# car.net
KiCad netlist of a schematic drawn in Altium Designer
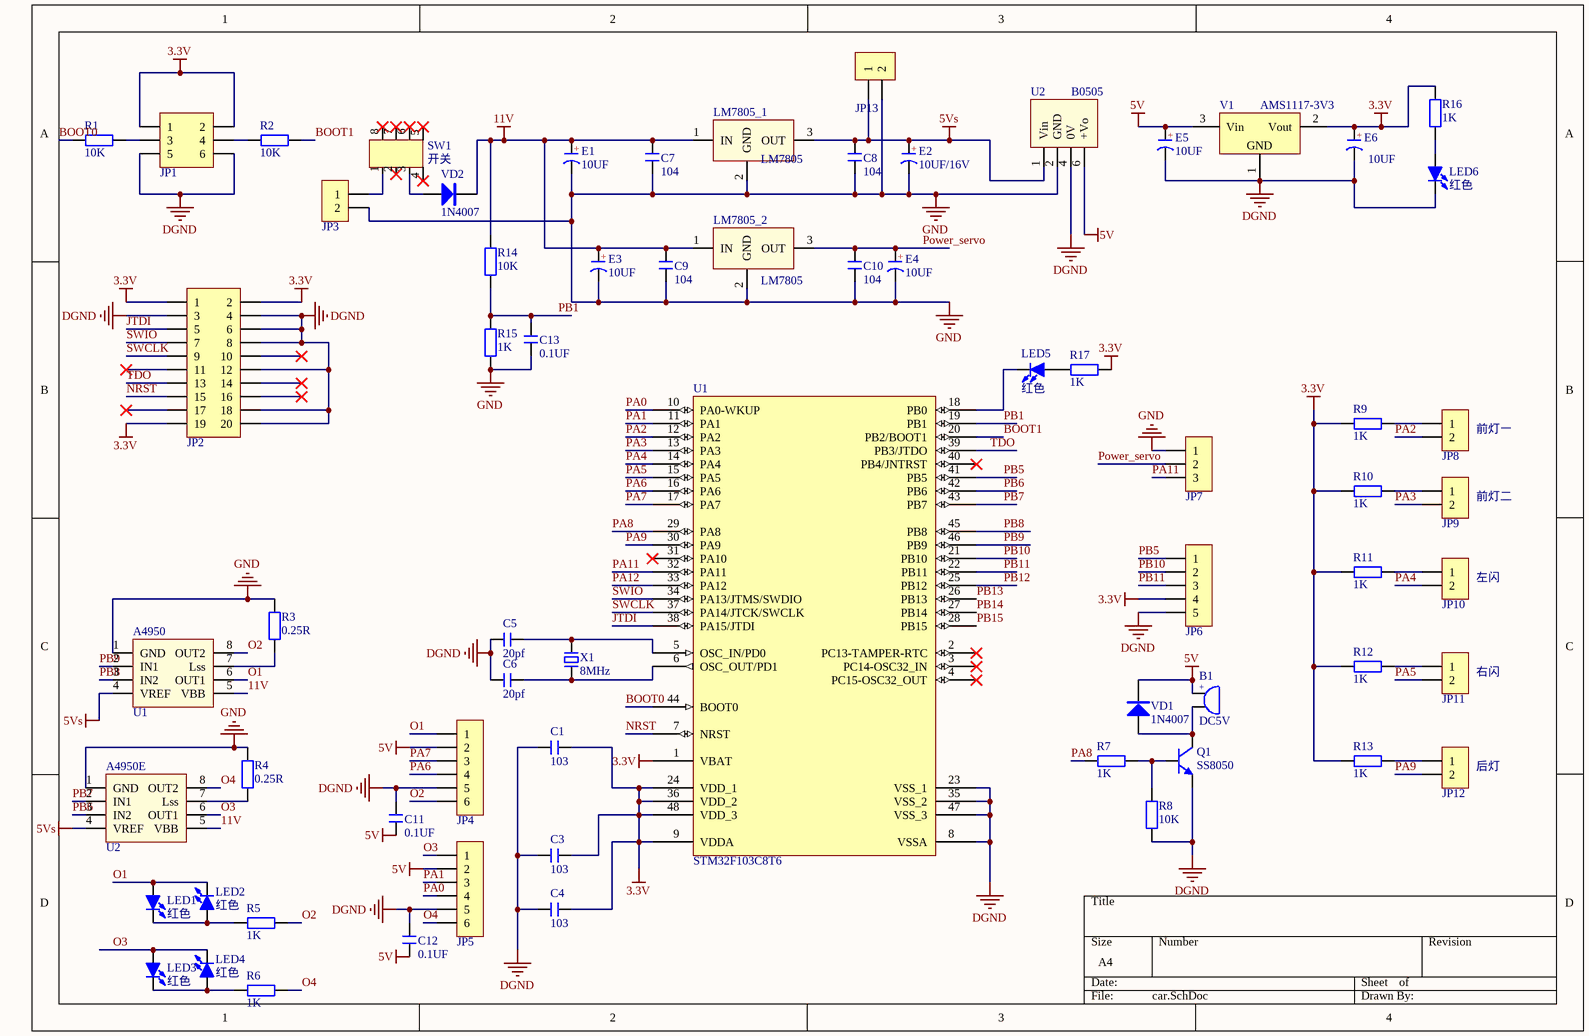
[diagram p0: car.SchDoc]

(export (version "E")
  (design (tool "Eeschema 10.0.6"))
  (components
    (comp (ref "A4950")
      (value "U1")
      (footprint "LC-SOIC-8_EP_150mil")
      (libsource (lib "A4950") (part "A4950"))
    )
    (comp (ref "A4950E")
      (value "U2")
      (footprint "LC-SOIC-8_EP_150mil")
      (libsource (lib "A4950") (part "A4950"))
    )
    (comp (ref "B1")
      (value "DC5V")
      (footprint "BEEP 7.6X12X9.5")
      (description "蜂鸣器")
      (fields (field (name "版权归属") "源创客"))
      (libsource (lib "未分类器件") (part "BEEP"))
    )
    (comp (ref "C1")
      (value "103")
      (footprint "C 0805")
      (description "无极性贴片电容")
      (fields (field (name "版权归属") "源创客"))
      (libsource (lib "电阻-电容-电感") (part "C"))
    )
    (comp (ref "C3")
      (value "103")
      (footprint "C 0805")
      (description "无极性贴片电容")
      (fields (field (name "版权归属") "源创客"))
      (libsource (lib "电阻-电容-电感") (part "C"))
    )
    (comp (ref "C4")
      (value "103")
      (footprint "C 0805")
      (description "无极性贴片电容")
      (fields (field (name "版权归属") "源创客"))
      (libsource (lib "电阻-电容-电感") (part "C"))
    )
    (comp (ref "C5")
      (value "20pf")
      (footprint "C 0805")
      (description "无极性贴片电容")
      (fields (field (name "版权归属") "源创客"))
      (libsource (lib "电阻-电容-电感") (part "C"))
    )
    (comp (ref "C6")
      (value "20pf")
      (footprint "C 0805")
      (description "无极性贴片电容")
      (fields (field (name "版权归属") "源创客"))
      (libsource (lib "电阻-电容-电感") (part "C"))
    )
    (comp (ref "C7")
      (value "104")
      (footprint "C 0805")
      (description "无极性贴片电容")
      (fields (field (name "版权归属") "源创客"))
      (libsource (lib "电阻-电容-电感") (part "C"))
    )
    (comp (ref "C8")
      (value "104")
      (footprint "C 0805")
      (description "无极性贴片电容")
      (fields (field (name "版权归属") "源创客"))
      (libsource (lib "电阻-电容-电感") (part "C"))
    )
    (comp (ref "C9")
      (value "104")
      (footprint "C 0805")
      (description "无极性贴片电容")
      (fields (field (name "版权归属") "源创客"))
      (libsource (lib "电阻-电容-电感") (part "C"))
    )
    (comp (ref "C10")
      (value "104")
      (footprint "C 0805")
      (description "无极性贴片电容")
      (fields (field (name "版权归属") "源创客"))
      (libsource (lib "电阻-电容-电感") (part "C"))
    )
    (comp (ref "C11")
      (value "0.1UF")
      (footprint "C 0805")
      (description "无极性贴片电容")
      (fields (field (name "版权归属") "源创客"))
      (libsource (lib "电阻-电容-电感") (part "C"))
    )
    (comp (ref "C12")
      (value "0.1UF")
      (footprint "C 0805")
      (description "无极性贴片电容")
      (fields (field (name "版权归属") "源创客"))
      (libsource (lib "电阻-电容-电感") (part "C"))
    )
    (comp (ref "C13")
      (value "0.1UF")
      (footprint "C 0805")
      (description "无极性贴片电容")
      (fields (field (name "版权归属") "源创客"))
      (libsource (lib "电阻-电容-电感") (part "C"))
    )
    (comp (ref "E1")
      (value "10UF")
      (footprint "CAP 2.5*5*11")
      (description "直插电解电容")
      (fields (field (name "版权归属") "源创客"))
      (libsource (lib "电阻-电容-电感") (part "C-CAP"))
    )
    (comp (ref "E2")
      (value "10UF/16V")
      (footprint "CAP 2.5*5*11")
      (description "直插电解电容")
      (fields (field (name "版权归属") "源创客"))
      (libsource (lib "电阻-电容-电感") (part "C-CAP"))
    )
    (comp (ref "E3")
      (value "10UF")
      (footprint "CAP 2.5*5*11")
      (description "直插电解电容")
      (fields (field (name "版权归属") "源创客"))
      (libsource (lib "电阻-电容-电感") (part "C-CAP"))
    )
    (comp (ref "E4")
      (value "10UF")
      (footprint "CAP 2.5*5*11")
      (description "直插电解电容")
      (fields (field (name "版权归属") "源创客"))
      (libsource (lib "电阻-电容-电感") (part "C-CAP"))
    )
    (comp (ref "E5")
      (value "10UF")
      (footprint "CS 2.0*5*8 - C")
      (description "直插固态电容")
      (fields (field (name "版权归属") "源创客"))
      (libsource (lib "电阻-电容-电感") (part "C-CS"))
    )
    (comp (ref "E6")
      (value "10UF")
      (footprint "CS 2.0*5*8 - C")
      (description "直插固态电容")
      (fields (field (name "版权归属") "源创客"))
      (libsource (lib "电阻-电容-电感") (part "C-CS"))
    )
    (comp (ref "JP1")
      (value "Header3X2")
      (footprint "HDR-3X2")
      (description "3*2P接插件")
      (fields (field (name "版权归属") "源创客"))
      (libsource (lib "接插件") (part "Header 3X2"))
    )
    (comp (ref "JP2")
      (value "Header 2X10")
      (footprint "IDC2.54-20P")
      (description "10*2P接插件")
      (fields (field (name "版权归属") "源创客"))
      (libsource (lib "接插件") (part "Header 10X2"))
    )
    (comp (ref "JP3")
      (value "HDR-1X2")
      (footprint "HDR-1X2")
      (description "2P接插件")
      (fields (field (name "版权归属") "源创客"))
      (libsource (lib "") (part "Header 2_2"))
    )
    (comp (ref "JP4")
      (value "HDR-1X6")
      (footprint "XH2.54-6P_H")
      (description "6P接插件")
      (fields (field (name "版权归属") "源创客"))
      (libsource (lib "接插件") (part "Header 6"))
    )
    (comp (ref "JP5")
      (value "HDR-1X6")
      (footprint "XH2.54-6P_H")
      (description "6P接插件")
      (fields (field (name "版权归属") "源创客"))
      (libsource (lib "接插件") (part "Header 6"))
    )
    (comp (ref "JP6")
      (value "HDR-1X5")
      (footprint "HDR-1X5")
      (description "5P接插件")
      (fields (field (name "版权归属") "源创客"))
      (libsource (lib "接插件") (part "Header 5"))
    )
    (comp (ref "JP7")
      (value "HDR-1X3")
      (footprint "HDR-1X3")
      (description "3P接插件")
      (fields (field (name "版权归属") "源创客"))
      (libsource (lib "接插件") (part "Header 3"))
    )
    (comp (ref "JP8")
      (value "HDR-1X2")
      (footprint "HDR-1X2")
      (description "2P接插件")
      (fields (field (name "版权归属") "源创客"))
      (libsource (lib "接插件") (part "Header 2"))
    )
    (comp (ref "JP9")
      (value "HDR-1X2")
      (footprint "HDR-1X2")
      (description "2P接插件")
      (fields (field (name "版权归属") "源创客"))
      (libsource (lib "接插件") (part "Header 2"))
    )
    (comp (ref "JP10")
      (value "HDR-1X2")
      (footprint "HDR-1X2")
      (description "2P接插件")
      (fields (field (name "版权归属") "源创客"))
      (libsource (lib "接插件") (part "Header 2"))
    )
    (comp (ref "JP11")
      (value "HDR-1X2")
      (footprint "HDR-1X2")
      (description "2P接插件")
      (fields (field (name "版权归属") "源创客"))
      (libsource (lib "接插件") (part "Header 2"))
    )
    (comp (ref "JP12")
      (value "HDR-1X2")
      (footprint "HDR-1X2")
      (description "2P接插件")
      (fields (field (name "版权归属") "源创客"))
      (libsource (lib "接插件") (part "Header 2"))
    )
    (comp (ref "JP13")
      (value "HDR-1X2")
      (footprint "HDR-1X2")
      (description "2P接插件")
      (fields (field (name "版权归属") "源创客"))
      (libsource (lib "") (part "Header 2_1"))
    )
    (comp (ref "LED1")
      (value "红色")
      (footprint "LED 1206G")
      (description "贴片LED")
      (fields (field (name "版权归属") "源创客"))
      (libsource (lib "LED") (part "LED-SMD"))
    )
    (comp (ref "LED2")
      (value "红色")
      (footprint "LED 1206G")
      (description "贴片LED")
      (fields (field (name "版权归属") "源创客"))
      (libsource (lib "LED") (part "LED-SMD"))
    )
    (comp (ref "LED3")
      (value "红色")
      (footprint "LED 1206G")
      (description "贴片LED")
      (fields (field (name "版权归属") "源创客"))
      (libsource (lib "LED") (part "LED-SMD"))
    )
    (comp (ref "LED4")
      (value "红色")
      (footprint "LED 1206G")
      (description "贴片LED")
      (fields (field (name "版权归属") "源创客"))
      (libsource (lib "LED") (part "LED-SMD"))
    )
    (comp (ref "LED5")
      (value "红色")
      (footprint "LED 1206Y")
      (description "贴片LED")
      (fields (field (name "版权归属") "源创客"))
      (libsource (lib "LED") (part "LED-SMD"))
    )
    (comp (ref "LED6")
      (value "红色")
      (footprint "LED 1206G")
      (description "贴片LED")
      (fields (field (name "版权归属") "源创客"))
      (libsource (lib "LED") (part "LED-SMD"))
    )
    (comp (ref "LM7805_1")
      (value "LM7805")
      (footprint "LC-TO-220(TO-220-3)")
      (libsource (lib "LM7805") (part "LM7805"))
    )
    (comp (ref "LM7805_2")
      (value "LM7805")
      (footprint "LC-TO-220(TO-220-3)")
      (libsource (lib "LM7805") (part "LM7805"))
    )
    (comp (ref "Q1")
      (value "SS8050")
      (footprint "SOT23-3N")
      (description "高频放大-NPN型")
      (fields (field (name "版权归属") "源创客"))
      (libsource (lib "三极管") (part "8050-SMD"))
    )
    (comp (ref "R1")
      (value "10K")
      (footprint "R 1206")
      (description "贴片电阻")
      (fields (field (name "版权归属") "源创客"))
      (libsource (lib "电阻-电容-电感") (part "R"))
    )
    (comp (ref "R2")
      (value "10K")
      (footprint "R 1206")
      (description "贴片电阻")
      (fields (field (name "版权归属") "源创客"))
      (libsource (lib "电阻-电容-电感") (part "R"))
    )
    (comp (ref "R3")
      (value "0.25R")
      (footprint "R 1206")
      (description "贴片电阻")
      (fields (field (name "版权归属") "源创客"))
      (libsource (lib "电阻-电容-电感") (part "R"))
    )
    (comp (ref "R4")
      (value "0.25R")
      (footprint "R 1206")
      (description "贴片电阻")
      (fields (field (name "版权归属") "源创客"))
      (libsource (lib "电阻-电容-电感") (part "R"))
    )
    (comp (ref "R5")
      (value "1K")
      (footprint "R 0805")
      (description "贴片电阻")
      (fields (field (name "版权归属") "源创客"))
      (libsource (lib "电阻-电容-电感") (part "R"))
    )
    (comp (ref "R6")
      (value "1K")
      (footprint "R 0805")
      (description "贴片电阻")
      (fields (field (name "版权归属") "源创客"))
      (libsource (lib "电阻-电容-电感") (part "R"))
    )
    (comp (ref "R7")
      (value "1K")
      (footprint "R 1206")
      (description "贴片电阻")
      (fields (field (name "版权归属") "源创客"))
      (libsource (lib "电阻-电容-电感") (part "R"))
    )
    (comp (ref "R8")
      (value "10K")
      (footprint "R 1206")
      (description "贴片电阻")
      (fields (field (name "版权归属") "源创客"))
      (libsource (lib "电阻-电容-电感") (part "R"))
    )
    (comp (ref "R9")
      (value "1K")
      (footprint "R 1206")
      (description "贴片电阻")
      (fields (field (name "版权归属") "源创客"))
      (libsource (lib "电阻-电容-电感") (part "R"))
    )
    (comp (ref "R10")
      (value "1K")
      (footprint "R 1206")
      (description "贴片电阻")
      (fields (field (name "版权归属") "源创客"))
      (libsource (lib "电阻-电容-电感") (part "R"))
    )
    (comp (ref "R11")
      (value "1K")
      (footprint "R 1206")
      (description "贴片电阻")
      (fields (field (name "版权归属") "源创客"))
      (libsource (lib "电阻-电容-电感") (part "R"))
    )
    (comp (ref "R12")
      (value "1K")
      (footprint "R 1206")
      (description "贴片电阻")
      (fields (field (name "版权归属") "源创客"))
      (libsource (lib "电阻-电容-电感") (part "R"))
    )
    (comp (ref "R13")
      (value "1K")
      (footprint "R 1206")
      (description "贴片电阻")
      (fields (field (name "版权归属") "源创客"))
      (libsource (lib "电阻-电容-电感") (part "R"))
    )
    (comp (ref "R14")
      (value "10K")
      (footprint "R 1206")
      (description "贴片电阻")
      (fields (field (name "版权归属") "源创客"))
      (libsource (lib "电阻-电容-电感") (part "R"))
    )
    (comp (ref "R15")
      (value "1K")
      (footprint "R 0805")
      (description "贴片电阻")
      (fields (field (name "版权归属") "源创客"))
      (libsource (lib "电阻-电容-电感") (part "R"))
    )
    (comp (ref "R16")
      (value "1K")
      (footprint "R 1206")
      (description "贴片电阻")
      (fields (field (name "版权归属") "源创客"))
      (libsource (lib "电阻-电容-电感") (part "R"))
    )
    (comp (ref "R17")
      (value "1K")
      (footprint "R 1206")
      (description "贴片电阻")
      (fields (field (name "版权归属") "源创客"))
      (libsource (lib "电阻-电容-电感") (part "R"))
    )
    (comp (ref "SW1") (value "开关") (footprint "PCBComponent_1") (libsource (lib "开关") (part "开关")))
    (comp (ref "U1")
      (value "STM32F103C8T6")
      (footprint "LQFP48 7X7_M")
      (description "Flaah:64/RAM:20/IO:36")
      (fields (field (name "版权归属") "源创客"))
      (libsource (lib "STM32系列单片机") (part "STM32F103C8T6"))
    )
    (comp (ref "U2") (value "B0505") (footprint "B0505") (libsource (lib "B0505") (part "B0505")))
    (comp (ref "V1")
      (value "AMS1117-3V3")
      (footprint "SOT223_L")
      (description "三端稳压芯片")
      (fields (field (name "版权归属") "源创客"))
      (libsource (lib "IC芯片") (part "AMS1117"))
    )
    (comp (ref "VD1")
      (value "1N4007")
      (footprint "DO-41")
      (description "整流二极管")
      (fields (field (name "版权归属") "源创客"))
      (libsource (lib "二极管-整流桥") (part "1N4007"))
    )
    (comp (ref "VD2")
      (value "1N4007")
      (footprint "DO-41")
      (description "整流二极管")
      (fields (field (name "版权归属") "源创客"))
      (libsource (lib "二极管-整流桥") (part "1N4007"))
    )
    (comp (ref "X1")
      (value "8MHz")
      (footprint "XTAL-49S SMD")
      (description "2脚晶振")
      (fields (field (name "版权归属") "源创客"))
      (libsource (lib "保险丝-晶振") (part "XTAL-2"))
    )
  )
  (nets
    (net (code "1") (name "/BOOT0") (class "Default")
      (node (ref "R1") (pin "1") (pinfunction "1_1") (pintype "passive"))
      (node (ref "U1") (pin "44") (pinfunction "BOOT0_44") (pintype "input"))
    )
    (net (code "2") (name "/BOOT1") (class "Default")
      (node (ref "R2") (pin "2") (pinfunction "2_2") (pintype "passive"))
      (node (ref "U1") (pin "20") (pinfunction "PB2/BOOT1_20") (pintype "bidirectional"))
    )
    (net (code "3") (name "/JTDI") (class "Default")
      (node (ref "JP2") (pin "5") (pinfunction "5_5") (pintype "passive"))
      (node (ref "U1") (pin "38") (pinfunction "PA15/JTDI_38") (pintype "bidirectional"))
    )
    (net (code "4") (name "/NRST") (class "Default")
      (node (ref "JP2") (pin "15") (pinfunction "15_15") (pintype "passive"))
      (node (ref "U1") (pin "7") (pinfunction "NRST_7") (pintype "bidirectional"))
    )
    (net (code "5") (name "/O1") (class "Default")
      (node (ref "A4950") (pin "6") (pinfunction "OUT1_6") (pintype "passive"))
      (node (ref "JP4") (pin "1") (pinfunction "1_1") (pintype "passive"))
      (node (ref "LED1") (pin "1") (pinfunction "A_1") (pintype "passive"))
      (node (ref "LED2") (pin "2") (pinfunction "K_2") (pintype "passive"))
    )
    (net (code "6") (name "/O2") (class "Default")
      (node (ref "A4950") (pin "8") (pinfunction "OUT2_8") (pintype "passive"))
      (node (ref "JP4") (pin "6") (pinfunction "6_6") (pintype "passive"))
      (node (ref "R5") (pin "2") (pinfunction "2_2") (pintype "passive"))
    )
    (net (code "7") (name "/O3") (class "Default")
      (node (ref "A4950E") (pin "6") (pinfunction "OUT1_6") (pintype "passive"))
      (node (ref "JP5") (pin "1") (pinfunction "1_1") (pintype "passive"))
      (node (ref "LED3") (pin "1") (pinfunction "A_1") (pintype "passive"))
      (node (ref "LED4") (pin "2") (pinfunction "K_2") (pintype "passive"))
    )
    (net (code "8") (name "/O4") (class "Default")
      (node (ref "A4950E") (pin "8") (pinfunction "OUT2_8") (pintype "passive"))
      (node (ref "JP5") (pin "6") (pinfunction "6_6") (pintype "passive"))
      (node (ref "R6") (pin "2") (pinfunction "2_2") (pintype "passive"))
    )
    (net (code "9") (name "/PA0") (class "Default")
      (node (ref "JP5") (pin "4") (pinfunction "4_4") (pintype "passive"))
      (node (ref "U1") (pin "10") (pinfunction "PA0-WKUP_10") (pintype "bidirectional"))
    )
    (net (code "10") (name "/PA1") (class "Default")
      (node (ref "JP5") (pin "3") (pinfunction "3_3") (pintype "passive"))
      (node (ref "U1") (pin "11") (pinfunction "PA1_11") (pintype "bidirectional"))
    )
    (net (code "11") (name "/PA2") (class "Default")
      (node (ref "JP8") (pin "2") (pinfunction "2_2") (pintype "passive"))
      (node (ref "U1") (pin "12") (pinfunction "PA2_12") (pintype "bidirectional"))
    )
    (net (code "12") (name "/PA3") (class "Default")
      (node (ref "JP9") (pin "2") (pinfunction "2_2") (pintype "passive"))
      (node (ref "U1") (pin "13") (pinfunction "PA3_13") (pintype "bidirectional"))
    )
    (net (code "13") (name "/PA4") (class "Default")
      (node (ref "JP10") (pin "2") (pinfunction "2_2") (pintype "passive"))
      (node (ref "U1") (pin "14") (pinfunction "PA4_14") (pintype "bidirectional"))
    )
    (net (code "14") (name "/PA5") (class "Default")
      (node (ref "JP11") (pin "2") (pinfunction "2_2") (pintype "passive"))
      (node (ref "U1") (pin "15") (pinfunction "PA5_15") (pintype "bidirectional"))
    )
    (net (code "15") (name "/PA6") (class "Default")
      (node (ref "JP4") (pin "4") (pinfunction "4_4") (pintype "passive"))
      (node (ref "U1") (pin "16") (pinfunction "PA6_16") (pintype "bidirectional"))
    )
    (net (code "16") (name "/PA7") (class "Default")
      (node (ref "JP4") (pin "3") (pinfunction "3_3") (pintype "passive"))
      (node (ref "U1") (pin "17") (pinfunction "PA7_17") (pintype "bidirectional"))
    )
    (net (code "17") (name "/PA8") (class "Default")
      (node (ref "R7") (pin "1") (pinfunction "1_1") (pintype "passive"))
      (node (ref "U1") (pin "29") (pinfunction "PA8_29") (pintype "bidirectional"))
    )
    (net (code "18") (name "/PA9") (class "Default")
      (node (ref "JP12") (pin "2") (pinfunction "2_2") (pintype "passive"))
      (node (ref "U1") (pin "30") (pinfunction "PA9_30") (pintype "bidirectional"))
    )
    (net (code "19") (name "/PA11") (class "Default")
      (node (ref "JP7") (pin "3") (pinfunction "3_3") (pintype "passive"))
      (node (ref "U1") (pin "32") (pinfunction "PA11_32") (pintype "bidirectional"))
    )
    (net (code "20") (name "/PA12") (class "Default")
      (node (ref "U1") (pin "33") (pinfunction "PA12_33") (pintype "bidirectional"))
    )
    (net (code "21") (name "/PB1") (class "Default")
      (node (ref "C13") (pin "2") (pinfunction "2_2") (pintype "passive"))
      (node (ref "R14") (pin "1") (pinfunction "1_1") (pintype "passive"))
      (node (ref "R15") (pin "1") (pinfunction "1_1") (pintype "passive"))
      (node (ref "U1") (pin "19") (pinfunction "PB1_19") (pintype "bidirectional"))
    )
    (net (code "22") (name "/PB5") (class "Default")
      (node (ref "JP6") (pin "1") (pinfunction "1_1") (pintype "passive"))
      (node (ref "U1") (pin "41") (pinfunction "PB5_41") (pintype "bidirectional"))
    )
    (net (code "23") (name "/PB6") (class "Default")
      (node (ref "A4950E") (pin "3") (pinfunction "IN2_3") (pintype "passive"))
      (node (ref "U1") (pin "42") (pinfunction "PB6_42") (pintype "bidirectional"))
    )
    (net (code "24") (name "/PB7") (class "Default")
      (node (ref "A4950E") (pin "2") (pinfunction "IN1_2") (pintype "passive"))
      (node (ref "U1") (pin "43") (pinfunction "PB7_43") (pintype "bidirectional"))
    )
    (net (code "25") (name "/PB8") (class "Default")
      (node (ref "A4950") (pin "3") (pinfunction "IN2_3") (pintype "passive"))
      (node (ref "U1") (pin "45") (pinfunction "PB8_45") (pintype "bidirectional"))
    )
    (net (code "26") (name "/PB9") (class "Default")
      (node (ref "A4950") (pin "2") (pinfunction "IN1_2") (pintype "passive"))
      (node (ref "U1") (pin "46") (pinfunction "PB9_46") (pintype "bidirectional"))
    )
    (net (code "27") (name "/PB10") (class "Default")
      (node (ref "JP6") (pin "2") (pinfunction "2_2") (pintype "passive"))
      (node (ref "U1") (pin "21") (pinfunction "PB10_21") (pintype "bidirectional"))
    )
    (net (code "28") (name "/PB11") (class "Default")
      (node (ref "JP6") (pin "3") (pinfunction "3_3") (pintype "passive"))
      (node (ref "U1") (pin "22") (pinfunction "PB11_22") (pintype "bidirectional"))
    )
    (net (code "29") (name "/PB12") (class "Default")
      (node (ref "U1") (pin "25") (pinfunction "PB12_25") (pintype "bidirectional"))
    )
    (net (code "30") (name "/PB13") (class "Default")
      (node (ref "U1") (pin "26") (pinfunction "PB13_26") (pintype "bidirectional"))
    )
    (net (code "31") (name "/PB14") (class "Default")
      (node (ref "U1") (pin "27") (pinfunction "PB14_27") (pintype "bidirectional"))
    )
    (net (code "32") (name "/PB15") (class "Default")
      (node (ref "U1") (pin "28") (pinfunction "PB15_28") (pintype "bidirectional"))
    )
    (net (code "33") (name "/Power_servo") (class "Default")
      (node (ref "C10") (pin "2") (pinfunction "2_2") (pintype "passive"))
      (node (ref "E4") (pin "1") (pinfunction "A_1") (pintype "passive"))
      (node (ref "JP7") (pin "2") (pinfunction "2_2") (pintype "passive"))
      (node (ref "LM7805_2") (pin "3") (pinfunction "OUT_3") (pintype "passive"))
    )
    (net (code "34") (name "/SWCLK") (class "Default")
      (node (ref "JP2") (pin "9") (pinfunction "9_9") (pintype "passive"))
      (node (ref "U1") (pin "37") (pinfunction "PA14/JTCK/SWCLK_37") (pintype "bidirectional"))
    )
    (net (code "35") (name "/SWIO") (class "Default")
      (node (ref "JP2") (pin "7") (pinfunction "7_7") (pintype "passive"))
      (node (ref "U1") (pin "34") (pinfunction "PA13/JTMS/SWDIO_34") (pintype "bidirectional"))
    )
    (net (code "36") (name "/TDO") (class "Default")
      (node (ref "JP2") (pin "13") (pinfunction "13_13") (pintype "passive"))
      (node (ref "U1") (pin "39") (pinfunction "PB3/JTDO_39") (pintype "bidirectional"))
    )
    (net (code "37") (name "3.3V") (class "Default")
      (node (ref "C1") (pin "2") (pinfunction "2_2") (pintype "passive"))
      (node (ref "C3") (pin "2") (pinfunction "2_2") (pintype "passive"))
      (node (ref "C4") (pin "2") (pinfunction "2_2") (pintype "passive"))
      (node (ref "E6") (pin "1") (pinfunction "A_1") (pintype "passive"))
      (node (ref "JP1") (pin "1") (pinfunction "1_1") (pintype "passive"))
      (node (ref "JP1") (pin "2") (pinfunction "2_2") (pintype "passive"))
      (node (ref "JP2") (pin "1") (pinfunction "1_1") (pintype "passive"))
      (node (ref "JP2") (pin "19") (pinfunction "19_19") (pintype "passive"))
      (node (ref "JP2") (pin "2") (pinfunction "2_2") (pintype "passive"))
      (node (ref "JP6") (pin "4") (pinfunction "4_4") (pintype "passive"))
      (node (ref "R10") (pin "1") (pinfunction "1_1") (pintype "passive"))
      (node (ref "R11") (pin "1") (pinfunction "1_1") (pintype "passive"))
      (node (ref "R12") (pin "1") (pinfunction "1_1") (pintype "passive"))
      (node (ref "R13") (pin "1") (pinfunction "1_1") (pintype "passive"))
      (node (ref "R16") (pin "2") (pinfunction "2_2") (pintype "passive"))
      (node (ref "R17") (pin "1") (pinfunction "1_1") (pintype "passive"))
      (node (ref "R9") (pin "1") (pinfunction "1_1") (pintype "passive"))
      (node (ref "U1") (pin "1") (pinfunction "VBAT_1") (pintype "power_in"))
      (node (ref "U1") (pin "24") (pinfunction "VDD_1_24") (pintype "power_in"))
      (node (ref "U1") (pin "36") (pinfunction "VDD_2_36") (pintype "power_in"))
      (node (ref "U1") (pin "48") (pinfunction "VDD_3_48") (pintype "power_in"))
      (node (ref "U1") (pin "9") (pinfunction "VDDA_9") (pintype "power_in"))
      (node (ref "V1") (pin "2") (pinfunction "Vout_2") (pintype "passive"))
    )
    (net (code "38") (name "5V") (class "Default")
      (node (ref "B1") (pin "1") (pinfunction "1_1") (pintype "passive"))
      (node (ref "C11") (pin "1") (pinfunction "1_1") (pintype "passive"))
      (node (ref "C12") (pin "1") (pinfunction "1_1") (pintype "passive"))
      (node (ref "E5") (pin "1") (pinfunction "A_1") (pintype "passive"))
      (node (ref "JP4") (pin "2") (pinfunction "2_2") (pintype "passive"))
      (node (ref "JP5") (pin "2") (pinfunction "2_2") (pintype "passive"))
      (node (ref "U2") (pin "6") (pinfunction "+Vo_6") (pintype "passive"))
      (node (ref "V1") (pin "3") (pinfunction "Vin_3") (pintype "passive"))
      (node (ref "VD1") (pin "2") (pinfunction "K_2") (pintype "passive"))
    )
    (net (code "39") (name "5Vs") (class "Default")
      (node (ref "A4950") (pin "4") (pinfunction "VREF_4") (pintype "passive"))
      (node (ref "A4950E") (pin "4") (pinfunction "VREF_4") (pintype "passive"))
      (node (ref "C8") (pin "2") (pinfunction "2_2") (pintype "passive"))
      (node (ref "E2") (pin "1") (pinfunction "A_1") (pintype "passive"))
      (node (ref "JP13") (pin "1") (pinfunction "1_1") (pintype "passive"))
      (node (ref "LM7805_1") (pin "3") (pinfunction "OUT_3") (pintype "passive"))
      (node (ref "U2") (pin "1") (pinfunction "Vin_1") (pintype "passive"))
    )
    (net (code "40") (name "11V") (class "Default")
      (node (ref "A4950") (pin "5") (pinfunction "VBB_5") (pintype "passive"))
      (node (ref "A4950E") (pin "5") (pinfunction "VBB_5") (pintype "passive"))
      (node (ref "C7") (pin "2") (pinfunction "2_2") (pintype "passive"))
      (node (ref "C9") (pin "2") (pinfunction "2_2") (pintype "passive"))
      (node (ref "E1") (pin "1") (pinfunction "A_1") (pintype "passive"))
      (node (ref "E3") (pin "1") (pinfunction "A_1") (pintype "passive"))
      (node (ref "LM7805_1") (pin "1") (pinfunction "IN_1") (pintype "passive"))
      (node (ref "LM7805_2") (pin "1") (pinfunction "IN_1") (pintype "passive"))
      (node (ref "R14") (pin "2") (pinfunction "2_2") (pintype "passive"))
      (node (ref "VD2") (pin "2") (pinfunction "K_2") (pintype "passive"))
    )
    (net (code "41") (name "DGND") (class "Default")
      (node (ref "C1") (pin "1") (pinfunction "1_1") (pintype "passive"))
      (node (ref "C11") (pin "2") (pinfunction "2_2") (pintype "passive"))
      (node (ref "C12") (pin "2") (pinfunction "2_2") (pintype "passive"))
      (node (ref "C3") (pin "1") (pinfunction "1_1") (pintype "passive"))
      (node (ref "C4") (pin "1") (pinfunction "1_1") (pintype "passive"))
      (node (ref "C5") (pin "1") (pinfunction "1_1") (pintype "passive"))
      (node (ref "C6") (pin "1") (pinfunction "1_1") (pintype "passive"))
      (node (ref "E5") (pin "2") (pinfunction "K_2") (pintype "passive"))
      (node (ref "E6") (pin "2") (pinfunction "K_2") (pintype "passive"))
      (node (ref "JP1") (pin "5") (pinfunction "5_5") (pintype "passive"))
      (node (ref "JP1") (pin "6") (pinfunction "6_6") (pintype "passive"))
      (node (ref "JP2") (pin "12") (pinfunction "12_12") (pintype "passive"))
      (node (ref "JP2") (pin "18") (pinfunction "18_18") (pintype "passive"))
      (node (ref "JP2") (pin "20") (pinfunction "20_20") (pintype "passive"))
      (node (ref "JP2") (pin "3") (pinfunction "3_3") (pintype "passive"))
      (node (ref "JP2") (pin "4") (pinfunction "4_4") (pintype "passive"))
      (node (ref "JP2") (pin "6") (pinfunction "6_6") (pintype "passive"))
      (node (ref "JP2") (pin "8") (pinfunction "8_8") (pintype "passive"))
      (node (ref "JP4") (pin "5") (pinfunction "5_5") (pintype "passive"))
      (node (ref "JP5") (pin "5") (pinfunction "5_5") (pintype "passive"))
      (node (ref "JP6") (pin "5") (pinfunction "5_5") (pintype "passive"))
      (node (ref "LED6") (pin "2") (pinfunction "K_2") (pintype "passive"))
      (node (ref "Q1") (pin "2") (pinfunction "E_2") (pintype "passive"))
      (node (ref "R8") (pin "1") (pinfunction "1_1") (pintype "passive"))
      (node (ref "U1") (pin "23") (pinfunction "VSS_1_23") (pintype "power_in"))
      (node (ref "U1") (pin "35") (pinfunction "VSS_2_35") (pintype "power_in"))
      (node (ref "U1") (pin "47") (pinfunction "VSS_3_47") (pintype "power_in"))
      (node (ref "U1") (pin "8") (pinfunction "VSSA_8") (pintype "power_in"))
      (node (ref "U2") (pin "4") (pinfunction "0V_4") (pintype "passive"))
      (node (ref "V1") (pin "1") (pinfunction "GND_1") (pintype "passive"))
    )
    (net (code "42") (name "GND") (class "Default")
      (node (ref "A4950") (pin "1") (pinfunction "GND_1") (pintype "passive"))
      (node (ref "A4950E") (pin "1") (pinfunction "GND_1") (pintype "passive"))
      (node (ref "C10") (pin "1") (pinfunction "1_1") (pintype "passive"))
      (node (ref "C13") (pin "1") (pinfunction "1_1") (pintype "passive"))
      (node (ref "C7") (pin "1") (pinfunction "1_1") (pintype "passive"))
      (node (ref "C8") (pin "1") (pinfunction "1_1") (pintype "passive"))
      (node (ref "C9") (pin "1") (pinfunction "1_1") (pintype "passive"))
      (node (ref "E1") (pin "2") (pinfunction "K_2") (pintype "passive"))
      (node (ref "E2") (pin "2") (pinfunction "K_2") (pintype "passive"))
      (node (ref "E3") (pin "2") (pinfunction "K_2") (pintype "passive"))
      (node (ref "E4") (pin "2") (pinfunction "K_2") (pintype "passive"))
      (node (ref "JP13") (pin "2") (pinfunction "2_2") (pintype "passive"))
      (node (ref "JP3") (pin "2") (pinfunction "2_2") (pintype "passive"))
      (node (ref "JP7") (pin "1") (pinfunction "1_1") (pintype "passive"))
      (node (ref "LM7805_1") (pin "2") (pinfunction "GND_2") (pintype "passive"))
      (node (ref "LM7805_2") (pin "2") (pinfunction "GND_2") (pintype "passive"))
      (node (ref "R15") (pin "2") (pinfunction "2_2") (pintype "passive"))
      (node (ref "R3") (pin "2") (pinfunction "2_2") (pintype "passive"))
      (node (ref "R4") (pin "2") (pinfunction "2_2") (pintype "passive"))
      (node (ref "U2") (pin "2") (pinfunction "GND_2") (pintype "passive"))
    )
    (net (code "43") (name "Net-(A4950-Lss)") (class "Default")
      (node (ref "A4950") (pin "7") (pinfunction "Lss_7") (pintype "passive"))
      (node (ref "R3") (pin "1") (pinfunction "1_1") (pintype "passive"))
    )
    (net (code "44") (name "Net-(A4950E-Lss)") (class "Default")
      (node (ref "A4950E") (pin "7") (pinfunction "Lss_7") (pintype "passive"))
      (node (ref "R4") (pin "1") (pinfunction "1_1") (pintype "passive"))
    )
    (net (code "45") (name "Net-(JP1-Pad3)") (class "Default")
      (node (ref "JP1") (pin "3") (pinfunction "3_3") (pintype "passive"))
      (node (ref "R1") (pin "2") (pinfunction "2_2") (pintype "passive"))
    )
    (net (code "46") (name "Net-(JP1-Pad4)") (class "Default")
      (node (ref "JP1") (pin "4") (pinfunction "4_4") (pintype "passive"))
      (node (ref "R2") (pin "1") (pinfunction "1_1") (pintype "passive"))
    )
    (net (code "47") (name "Net-(JP3-Pad1)") (class "Default")
      (node (ref "JP3") (pin "1") (pinfunction "1_1") (pintype "passive"))
      (node (ref "SW1") (pin "1") (pintype "passive"))
    )
    (net (code "48") (name "Net-(JP8-Pad1)") (class "Default")
      (node (ref "JP8") (pin "1") (pinfunction "1_1") (pintype "passive"))
      (node (ref "R9") (pin "2") (pinfunction "2_2") (pintype "passive"))
    )
    (net (code "49") (name "Net-(JP9-Pad1)") (class "Default")
      (node (ref "JP9") (pin "1") (pinfunction "1_1") (pintype "passive"))
      (node (ref "R10") (pin "2") (pinfunction "2_2") (pintype "passive"))
    )
    (net (code "50") (name "Net-(JP10-Pad1)") (class "Default")
      (node (ref "JP10") (pin "1") (pinfunction "1_1") (pintype "passive"))
      (node (ref "R11") (pin "2") (pinfunction "2_2") (pintype "passive"))
    )
    (net (code "51") (name "Net-(JP11-Pad1)") (class "Default")
      (node (ref "JP11") (pin "1") (pinfunction "1_1") (pintype "passive"))
      (node (ref "R12") (pin "2") (pinfunction "2_2") (pintype "passive"))
    )
    (net (code "52") (name "Net-(JP12-Pad1)") (class "Default")
      (node (ref "JP12") (pin "1") (pinfunction "1_1") (pintype "passive"))
      (node (ref "R13") (pin "2") (pinfunction "2_2") (pintype "passive"))
    )
    (net (code "53") (name "Net-(LED1-K)") (class "Default")
      (node (ref "LED1") (pin "2") (pinfunction "K_2") (pintype "passive"))
      (node (ref "LED2") (pin "1") (pinfunction "A_1") (pintype "passive"))
      (node (ref "R5") (pin "1") (pinfunction "1_1") (pintype "passive"))
    )
    (net (code "54") (name "Net-(LED3-K)") (class "Default")
      (node (ref "LED3") (pin "2") (pinfunction "K_2") (pintype "passive"))
      (node (ref "LED4") (pin "1") (pinfunction "A_1") (pintype "passive"))
      (node (ref "R6") (pin "1") (pinfunction "1_1") (pintype "passive"))
    )
    (net (code "55") (name "Net-(LED5-A)") (class "Default")
      (node (ref "LED5") (pin "1") (pinfunction "A_1") (pintype "passive"))
      (node (ref "R17") (pin "2") (pinfunction "2_2") (pintype "passive"))
    )
    (net (code "56") (name "Net-(LED5-K)") (class "Default")
      (node (ref "LED5") (pin "2") (pinfunction "K_2") (pintype "passive"))
      (node (ref "U1") (pin "18") (pinfunction "PB0_18") (pintype "bidirectional"))
    )
    (net (code "57") (name "Net-(LED6-A)") (class "Default")
      (node (ref "LED6") (pin "1") (pinfunction "A_1") (pintype "passive"))
      (node (ref "R16") (pin "1") (pinfunction "1_1") (pintype "passive"))
    )
    (net (code "58") (name "Net-(Q1-B)") (class "Default")
      (node (ref "Q1") (pin "1") (pinfunction "B_1") (pintype "passive"))
      (node (ref "R7") (pin "2") (pinfunction "2_2") (pintype "passive"))
      (node (ref "R8") (pin "2") (pinfunction "2_2") (pintype "passive"))
    )
    (net (code "59") (name "Net-(Q1-C)") (class "Default")
      (node (ref "B1") (pin "2") (pinfunction "2_2") (pintype "passive"))
      (node (ref "Q1") (pin "3") (pinfunction "C_3") (pintype "passive"))
      (node (ref "VD1") (pin "1") (pinfunction "A_1") (pintype "passive"))
    )
    (net (code "60") (name "Net-(U1-OSC_IN{slash}PD0)") (class "Default")
      (node (ref "C5") (pin "2") (pinfunction "2_2") (pintype "passive"))
      (node (ref "U1") (pin "5") (pinfunction "OSC_IN/PD0_5") (pintype "input"))
      (node (ref "X1") (pin "2") (pinfunction "2_2") (pintype "passive"))
    )
    (net (code "61") (name "Net-(U1-OSC_OUT{slash}PD1)") (class "Default")
      (node (ref "C6") (pin "2") (pinfunction "2_2") (pintype "passive"))
      (node (ref "U1") (pin "6") (pinfunction "OSC_OUT/PD1_6") (pintype "output"))
      (node (ref "X1") (pin "1") (pinfunction "1_1") (pintype "passive"))
    )
    (net (code "62") (name "Net-(VD2-A)") (class "Default")
      (node (ref "SW1") (pin "3") (pintype "passive"))
      (node (ref "VD2") (pin "1") (pinfunction "A_1") (pintype "passive"))
    )
    (net (code "63") (name "unconnected-(JP2-Pad10)") (class "Default")
      (node (ref "JP2") (pin "10") (pinfunction "10_10") (pintype "passive+no_connect"))
    )
    (net (code "64") (name "unconnected-(JP2-Pad11)") (class "Default")
      (node (ref "JP2") (pin "11") (pinfunction "11_11") (pintype "passive+no_connect"))
    )
    (net (code "65") (name "unconnected-(JP2-Pad14)") (class "Default")
      (node (ref "JP2") (pin "14") (pinfunction "14_14") (pintype "passive+no_connect"))
    )
    (net (code "66") (name "unconnected-(JP2-Pad16)") (class "Default")
      (node (ref "JP2") (pin "16") (pinfunction "16_16") (pintype "passive+no_connect"))
    )
    (net (code "67") (name "unconnected-(JP2-Pad17)") (class "Default")
      (node (ref "JP2") (pin "17") (pinfunction "17_17") (pintype "passive+no_connect"))
    )
    (net (code "68") (name "unconnected-(SW1-Pad2)") (class "Default")
      (node (ref "SW1") (pin "2") (pintype "passive+no_connect"))
    )
    (net (code "69") (name "unconnected-(SW1-Pad4)") (class "Default")
      (node (ref "SW1") (pin "4") (pintype "passive+no_connect"))
    )
    (net (code "70") (name "unconnected-(SW1-Pad5)") (class "Default")
      (node (ref "SW1") (pin "5") (pintype "passive+no_connect"))
    )
    (net (code "71") (name "unconnected-(SW1-Pad6)") (class "Default")
      (node (ref "SW1") (pin "6") (pintype "passive+no_connect"))
    )
    (net (code "72") (name "unconnected-(SW1-Pad7)") (class "Default")
      (node (ref "SW1") (pin "7") (pintype "passive+no_connect"))
    )
    (net (code "73") (name "unconnected-(SW1-Pad8)") (class "Default")
      (node (ref "SW1") (pin "8") (pintype "passive+no_connect"))
    )
    (net (code "74") (name "unconnected-(U1-PA10-Pad31)") (class "Default")
      (node (ref "U1") (pin "31") (pinfunction "PA10_31") (pintype "bidirectional+no_connect"))
    )
    (net (code "75") (name "unconnected-(U1-PB4{slash}JNTRST-Pad40)") (class "Default")
      (node (ref "U1") (pin "40") (pinfunction "PB4/JNTRST_40") (pintype "bidirectional+no_connect"))
    )
    (net (code "76") (name "unconnected-(U1-PC13-TAMPER-RTC-Pad2)") (class "Default")
      (node (ref "U1") (pin "2") (pinfunction "PC13-TAMPER-RTC_2") (pintype "bidirectional+no_connect"))
    )
    (net (code "77") (name "unconnected-(U1-PC14-OSC32_IN-Pad3)") (class "Default")
      (node (ref "U1") (pin "3") (pinfunction "PC14-OSC32_IN_3") (pintype "bidirectional+no_connect"))
    )
    (net (code "78") (name "unconnected-(U1-PC15-OSC32_OUT-Pad4)") (class "Default")
      (node (ref "U1") (pin "4") (pinfunction "PC15-OSC32_OUT_4") (pintype "bidirectional+no_connect"))
    )
  )
)
